# SD_Card.net
KiCad netlist of a schematic drawn in EAGLE
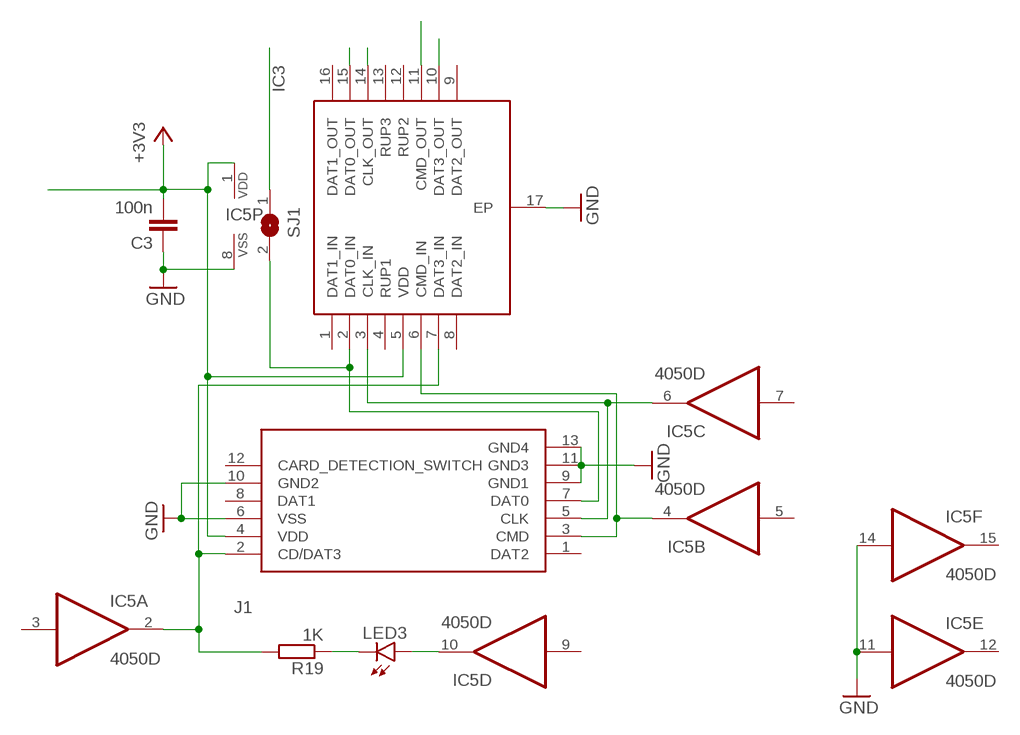
[diagram p0: schematic, sheet 1]

(export (version "E")
  (design (tool "Eeschema 10.0.6"))
  (components
    (comp (ref "C3")
      (value "100n")
      (footprint "eagle-import:C1206K")
      (libsource (lib "eagle-import") (part "C-EUC1206K"))
    )
    (comp (ref "IC3")
      (value "ECLAMP2410P.TCT")
      (footprint "eagle-import:SON50P160X400X65-17N")
      (fields (field (name "RS_PART_NUMBER") "6910638"))
      (libsource (lib "eagle-import") (part "ECLAMP2410P.TCT"))
    )
    (comp (ref "IC5")
      (value "4050D")
      (footprint "eagle-import:SO16")
      (libsource (lib "eagle-import") (part "4050D"))
    )
    (comp (ref "J1")
      (value "DM3CS-SF")
      (footprint "eagle-import:DM3CS-SF")
      (fields (field (name "RS_PART_NUMBER") "1664833"))
      (libsource (lib "eagle-import") (part "DM3CS-SF"))
    )
    (comp (ref "LED3")
      (value "LG_T679-E1F1-1")
      (footprint "eagle-import:PLCC2")
      (libsource (lib "eagle-import") (part "_T679-?-1E1F1LG"))
    )
    (comp (ref "R19")
      (value "1K")
      (footprint "eagle-import:R1206")
      (libsource (lib "eagle-import") (part "R-EU_R1206"))
    )
    (comp (ref "SJ1") (value "SJ") (footprint "eagle-import:SJ") (libsource (lib "eagle-import") (part "SJ")))
  )
  (nets
    (net (code "1") (name "+3V3") (class "Default")
      (node (ref "C3") (pin "2") (pinfunction "2_2") (pintype "passive"))
      (node (ref "IC3") (pin "5") (pinfunction "VDD_5") (pintype "bidirectional"))
      (node (ref "IC5") (pin "1") (pinfunction "VDD_1") (pintype "power_in"))
      (node (ref "J1") (pin "4") (pinfunction "VDD_4") (pintype "bidirectional"))
    )
    (net (code "2") (name "/N$2") (class "Default")
      (node (ref "IC3") (pin "15") (pinfunction "DAT0_OUT_15") (pintype "bidirectional"))
      (node (ref "SJ1") (pin "1") (pinfunction "1_1") (pintype "passive"))
    )
    (net (code "3") (name "GND") (class "Default")
      (node (ref "C3") (pin "1") (pinfunction "1_1") (pintype "passive"))
      (node (ref "IC3") (pin "17") (pinfunction "EP_17") (pintype "bidirectional"))
      (node (ref "IC5") (pin "11") (pinfunction "I_11") (pintype "input"))
      (node (ref "IC5") (pin "14") (pinfunction "I_14") (pintype "input"))
      (node (ref "IC5") (pin "8") (pinfunction "VSS_8") (pintype "power_in"))
      (node (ref "J1") (pin "10") (pinfunction "GND2_10") (pintype "bidirectional"))
      (node (ref "J1") (pin "11") (pinfunction "GND3_11") (pintype "bidirectional"))
      (node (ref "J1") (pin "13") (pinfunction "GND4_13") (pintype "bidirectional"))
      (node (ref "J1") (pin "6") (pinfunction "VSS_6") (pintype "bidirectional"))
      (node (ref "J1") (pin "9") (pinfunction "GND1_9") (pintype "bidirectional"))
    )
    (net (code "4") (name "Net-(IC3-CLK_IN)") (class "Default")
      (node (ref "IC3") (pin "3") (pinfunction "CLK_IN_3") (pintype "bidirectional"))
      (node (ref "IC5") (pin "6") (pinfunction "O_6") (pintype "output"))
      (node (ref "J1") (pin "5") (pinfunction "CLK_5") (pintype "bidirectional"))
    )
    (net (code "5") (name "Net-(IC3-CMD_IN)") (class "Default")
      (node (ref "IC3") (pin "6") (pinfunction "CMD_IN_6") (pintype "bidirectional"))
      (node (ref "IC5") (pin "4") (pinfunction "O_4") (pintype "output"))
      (node (ref "J1") (pin "3") (pinfunction "CMD_3") (pintype "bidirectional"))
    )
    (net (code "6") (name "Net-(IC3-DAT0_IN)") (class "Default")
      (node (ref "IC3") (pin "2") (pinfunction "DAT0_IN_2") (pintype "bidirectional"))
      (node (ref "J1") (pin "7") (pinfunction "DAT0_7") (pintype "bidirectional"))
      (node (ref "SJ1") (pin "2") (pinfunction "2_2") (pintype "passive"))
    )
    (net (code "7") (name "Net-(IC3-DAT3_IN)") (class "Default")
      (node (ref "IC3") (pin "7") (pinfunction "DAT3_IN_7") (pintype "bidirectional"))
      (node (ref "IC5") (pin "2") (pinfunction "O_2") (pintype "output"))
      (node (ref "J1") (pin "2") (pinfunction "CD/DAT3_2") (pintype "bidirectional"))
      (node (ref "R19") (pin "2") (pinfunction "2_2") (pintype "passive"))
    )
    (net (code "8") (name "Net-(IC5D-O)") (class "Default")
      (node (ref "IC5") (pin "10") (pinfunction "O_10") (pintype "output"))
      (node (ref "LED3") (pin "A") (pinfunction "A_A") (pintype "passive"))
    )
    (net (code "9") (name "Net-(LED3-PadC)") (class "Default")
      (node (ref "LED3") (pin "C") (pinfunction "C_C") (pintype "passive"))
      (node (ref "R19") (pin "1") (pinfunction "1_1") (pintype "passive"))
    )
    (net (code "10") (name "unconnected-(IC3-CLK_OUT-Pad14)") (class "Default")
      (node (ref "IC3") (pin "14") (pinfunction "CLK_OUT_14") (pintype "bidirectional"))
    )
    (net (code "11") (name "unconnected-(IC3-CMD_OUT-Pad11)") (class "Default")
      (node (ref "IC3") (pin "11") (pinfunction "CMD_OUT_11") (pintype "bidirectional"))
    )
    (net (code "12") (name "unconnected-(IC3-DAT1_IN-Pad1)") (class "Default")
      (node (ref "IC3") (pin "1") (pinfunction "DAT1_IN_1") (pintype "bidirectional"))
    )
    (net (code "13") (name "unconnected-(IC3-DAT1_OUT-Pad16)") (class "Default")
      (node (ref "IC3") (pin "16") (pinfunction "DAT1_OUT_16") (pintype "bidirectional"))
    )
    (net (code "14") (name "unconnected-(IC3-DAT2_IN-Pad8)") (class "Default")
      (node (ref "IC3") (pin "8") (pinfunction "DAT2_IN_8") (pintype "bidirectional"))
    )
    (net (code "15") (name "unconnected-(IC3-DAT2_OUT-Pad9)") (class "Default")
      (node (ref "IC3") (pin "9") (pinfunction "DAT2_OUT_9") (pintype "bidirectional"))
    )
    (net (code "16") (name "unconnected-(IC3-DAT3_OUT-Pad10)") (class "Default")
      (node (ref "IC3") (pin "10") (pinfunction "DAT3_OUT_10") (pintype "bidirectional"))
    )
    (net (code "17") (name "unconnected-(IC3-RUP1-Pad4)") (class "Default")
      (node (ref "IC3") (pin "4") (pinfunction "RUP1_4") (pintype "bidirectional"))
    )
    (net (code "18") (name "unconnected-(IC3-RUP2-Pad12)") (class "Default")
      (node (ref "IC3") (pin "12") (pinfunction "RUP2_12") (pintype "bidirectional"))
    )
    (net (code "19") (name "unconnected-(IC3-RUP3-Pad13)") (class "Default")
      (node (ref "IC3") (pin "13") (pinfunction "RUP3_13") (pintype "bidirectional"))
    )
    (net (code "20") (name "unconnected-(IC5A-I-Pad3)") (class "Default")
      (node (ref "IC5") (pin "3") (pinfunction "I_3") (pintype "input"))
    )
    (net (code "21") (name "unconnected-(IC5B-I-Pad5)") (class "Default")
      (node (ref "IC5") (pin "5") (pinfunction "I_5") (pintype "input"))
    )
    (net (code "22") (name "unconnected-(IC5C-I-Pad7)") (class "Default")
      (node (ref "IC5") (pin "7") (pinfunction "I_7") (pintype "input"))
    )
    (net (code "23") (name "unconnected-(IC5D-I-Pad9)") (class "Default")
      (node (ref "IC5") (pin "9") (pinfunction "I_9") (pintype "input"))
    )
    (net (code "24") (name "unconnected-(IC5E-O-Pad12)") (class "Default")
      (node (ref "IC5") (pin "12") (pinfunction "O_12") (pintype "output"))
    )
    (net (code "25") (name "unconnected-(IC5F-O-Pad15)") (class "Default")
      (node (ref "IC5") (pin "15") (pinfunction "O_15") (pintype "output"))
    )
    (net (code "26") (name "unconnected-(J1-CARD_DETECTION_SWITCH-Pad12)") (class "Default")
      (node (ref "J1") (pin "12") (pinfunction "CARD_DETECTION_SWITCH_12") (pintype "bidirectional"))
    )
    (net (code "27") (name "unconnected-(J1-DAT1-Pad8)") (class "Default")
      (node (ref "J1") (pin "8") (pinfunction "DAT1_8") (pintype "bidirectional"))
    )
    (net (code "28") (name "unconnected-(J1-DAT2-Pad1)") (class "Default")
      (node (ref "J1") (pin "1") (pinfunction "DAT2_1") (pintype "bidirectional"))
    )
  )
)
